# PWR_MGMT.net
KiCad netlist of a schematic drawn in Altium Designer
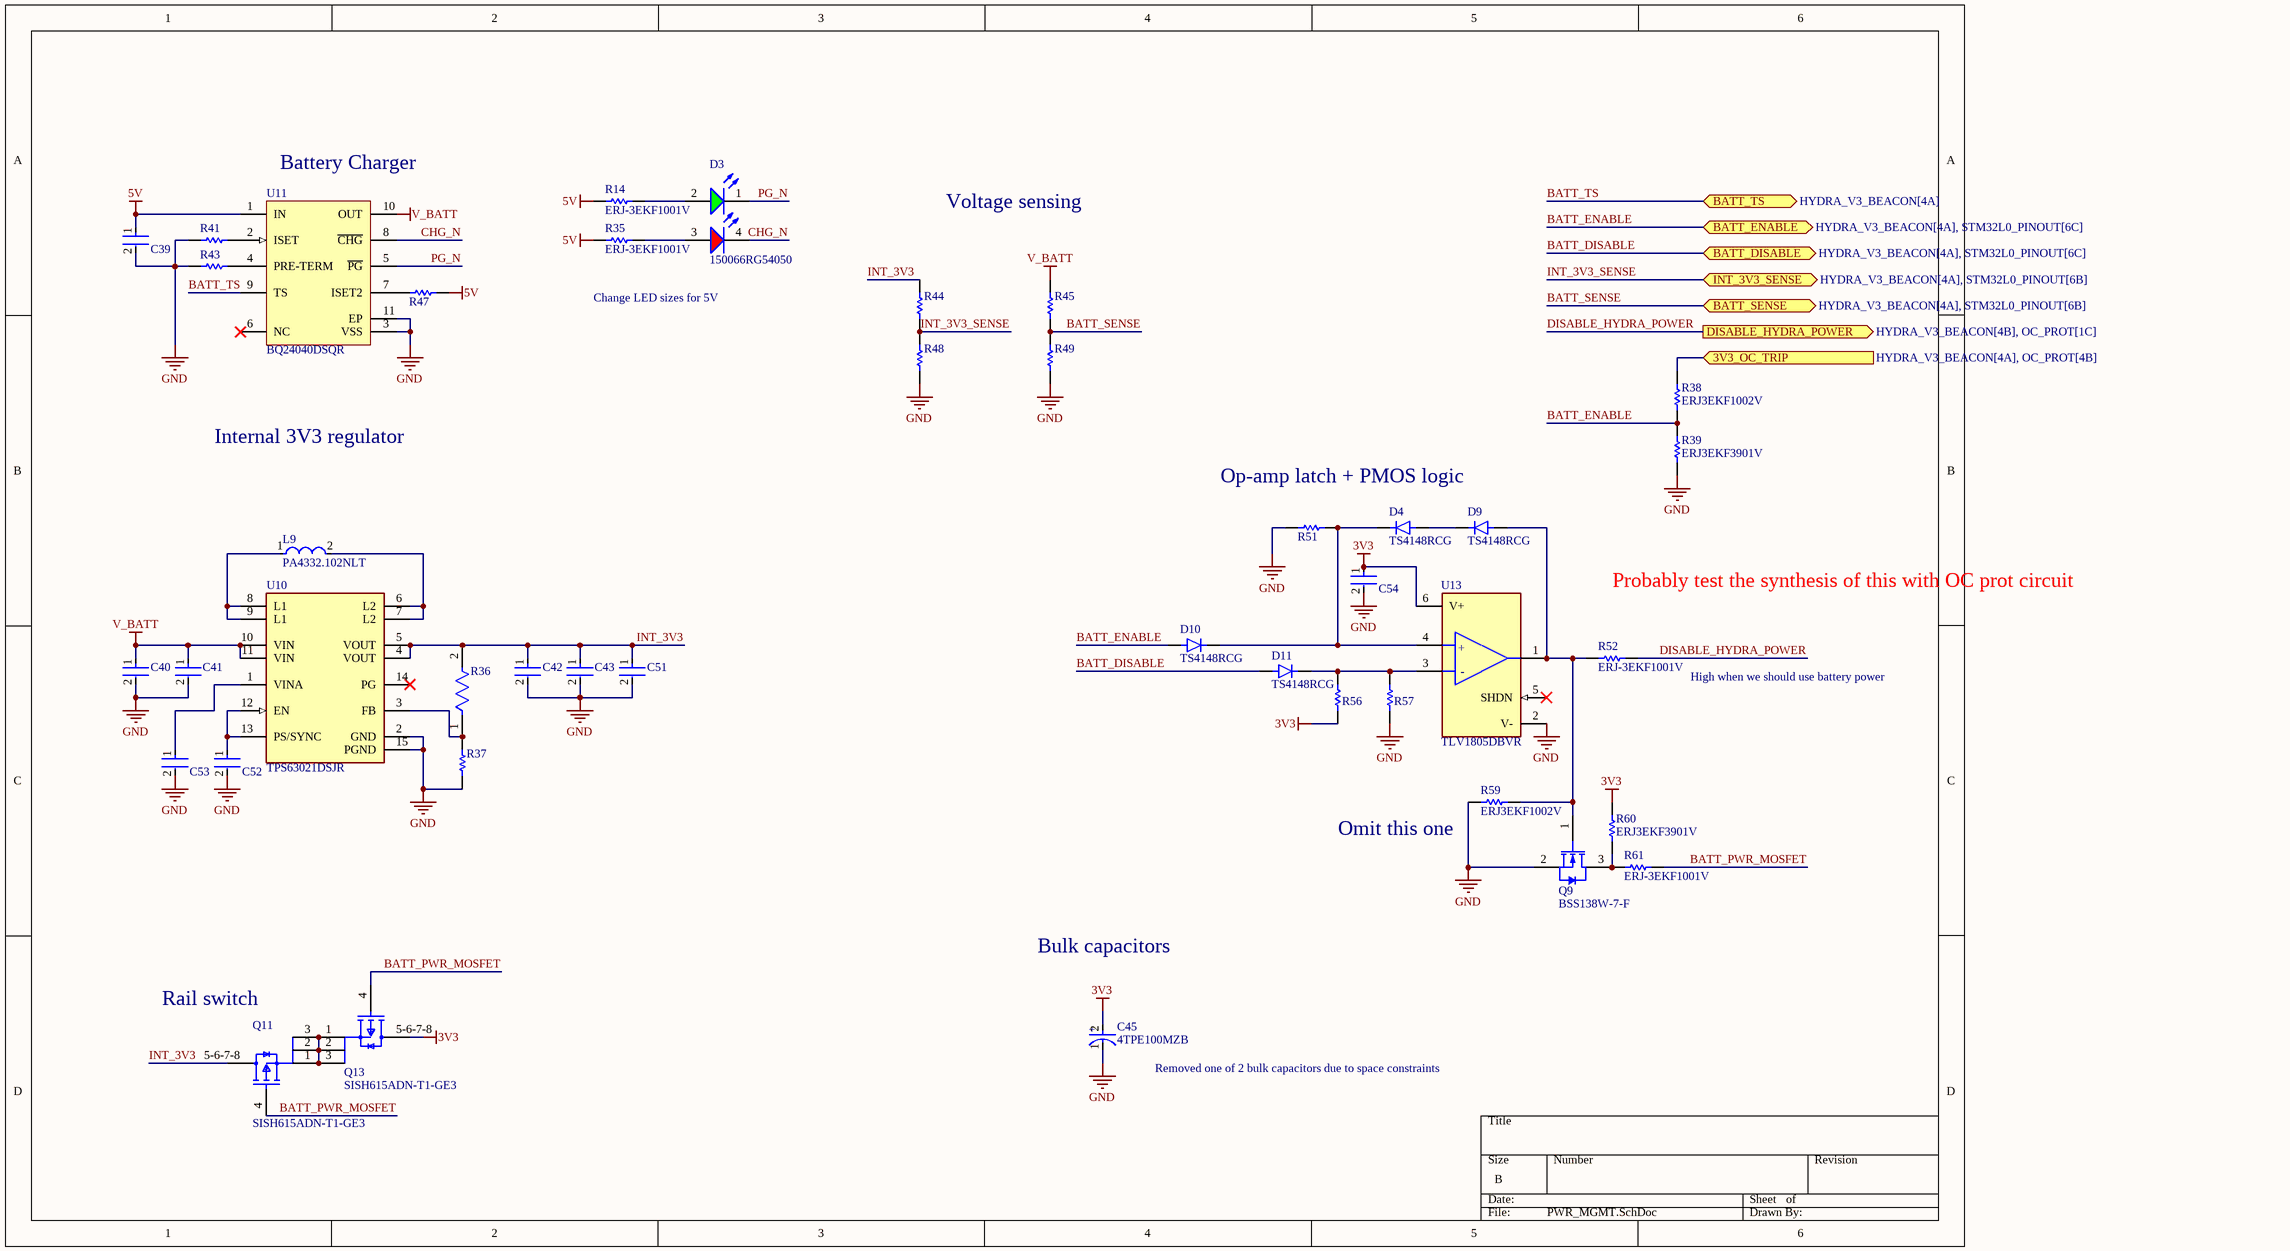
[diagram p0: PWR_MGMT.SchDoc]

(export (version "E")
  (design (tool "Eeschema 10.0.6"))
  (components
    (comp (ref "C39")
      (value "C0402C104K8PACTU")
      (footprint "FP-C0402-BB-MFG")
      (description "CAP CER 0.1UF 10V X5R 0402")
      (fields (field (name "MANUFACTURER") "Kemet") (field (name "TOLERANCE") "0.1"))
      (libsource (lib "Altium Content Vault") (part "b4654b650e69147ec39a6b967a45e02"))
    )
    (comp (ref "C40")
      (value "C0805C106K8PACTU")
      (footprint "FP-C0805C-DG-MFG")
      (description "CAP CER 10UF 10V X5R 0805")
      (fields (field (name "TOLERANCE") "10%") (field (name "MANUFACTURER") "Kemet"))
      (libsource (lib "Altium Content Vault") (part "11868f565c42a9108669ba33697ecf6"))
    )
    (comp (ref "C41")
      (value "C0805C106K8PACTU")
      (footprint "FP-C0805C-DG-MFG")
      (description "CAP CER 10UF 10V X5R 0805")
      (fields (field (name "TOLERANCE") "10%") (field (name "MANUFACTURER") "Kemet"))
      (libsource (lib "Altium Content Vault") (part "11868f565c42a9108669ba33697ecf6"))
    )
    (comp (ref "C42")
      (value "GRM21BR60J226ME39L")
      (footprint "FP-GRM21B-0_15-MFG")
      (description "Chip Multilayer Ceramic Capacitors for General Purpose, 0805, 22uF, X5R, 15%, 20%, 6.3V")
      (fields (field (name "VOLTAGE") "6.3V") (field (name "TOLERANCE") "20%"))
      (libsource (lib "Altium Content Vault") (part "b4654b650e69147ec39a6b967a45e02"))
    )
    (comp (ref "C43")
      (value "GRM21BR60J226ME39L")
      (footprint "FP-GRM21B-0_15-MFG")
      (description "Chip Multilayer Ceramic Capacitors for General Purpose, 0805, 22uF, X5R, 15%, 20%, 6.3V")
      (fields (field (name "VOLTAGE") "6.3V") (field (name "TOLERANCE") "20%"))
      (libsource (lib "Altium Content Vault") (part "b4654b650e69147ec39a6b967a45e02"))
    )
    (comp (ref "C45")
      (value "4TPE100MZB")
      (footprint "FP-POSCAP-B2-MFG")
      (description "Molded Tantalum Polymer Capacitor 100uF 20% 4V life 1000Hours SMD 1411")
      (fields (field (name "VOLTAGE") "4V") (field (name "TOLERANCE") "20%"))
      (libsource (lib "Altium Content Vault") (part "cf48714ba7e38822c1575c7ec0b6d1f"))
    )
    (comp (ref "C51")
      (value "GRM21BR60J226ME39L")
      (footprint "FP-GRM21B-0_15-MFG")
      (description "Chip Multilayer Ceramic Capacitors for General Purpose, 0805, 22uF, X5R, 15%, 20%, 6.3V")
      (fields (field (name "VOLTAGE") "6.3V") (field (name "TOLERANCE") "20%"))
      (libsource (lib "Altium Content Vault") (part "b4654b650e69147ec39a6b967a45e02"))
    )
    (comp (ref "C52")
      (value "C0402C104K8PACTU")
      (footprint "FP-C0402-BB-MFG")
      (description "CAP CER 0.1UF 10V X5R 0402")
      (fields (field (name "MANUFACTURER") "Kemet") (field (name "TOLERANCE") "0.1"))
      (libsource (lib "Altium Content Vault") (part "b4654b650e69147ec39a6b967a45e02"))
    )
    (comp (ref "C53")
      (value "C0402C104K8PACTU")
      (footprint "FP-C0402-BB-MFG")
      (description "CAP CER 0.1UF 10V X5R 0402")
      (fields (field (name "MANUFACTURER") "Kemet") (field (name "TOLERANCE") "0.1"))
      (libsource (lib "Altium Content Vault") (part "b4654b650e69147ec39a6b967a45e02"))
    )
    (comp (ref "C54")
      (value "C0402C104K8PACTU")
      (footprint "FP-C0402-BB-MFG")
      (description "CAP CER 0.1UF 10V X5R 0402")
      (fields (field (name "MANUFACTURER") "Kemet") (field (name "TOLERANCE") "0.1"))
      (libsource (lib "Altium Content Vault") (part "b4654b650e69147ec39a6b967a45e02"))
    )
    (comp (ref "D3")
      (value "150066RG54050")
      (footprint "WL-SBCD_0606")
      (description "Led, Red/Grn, 180Mcd/230Mcd, 624Nm/525Nm Rohs Compliant: Yes")
      (libsource (lib "uORocketry Hardware") (part "WL-SBCD_0606_Red & Green"))
    )
    (comp (ref "D4")
      (value "TS4148RCG")
      (footprint "TS4148RCG-Footprint-1")
      (description "SMD Si-Diode 75V 100mA 0603")
      (libsource (lib "uORocketry Hardware") (part "TS4148RCG"))
    )
    (comp (ref "D9")
      (value "TS4148RCG")
      (footprint "TS4148RCG-Footprint-1")
      (description "SMD Si-Diode 75V 100mA 0603")
      (libsource (lib "uORocketry Hardware") (part "TS4148RCG"))
    )
    (comp (ref "D10")
      (value "TS4148RCG")
      (footprint "TS4148RCG-Footprint-1")
      (description "SMD Si-Diode 75V 100mA 0603")
      (libsource (lib "uORocketry Hardware") (part "TS4148RCG"))
    )
    (comp (ref "D11")
      (value "TS4148RCG")
      (footprint "TS4148RCG-Footprint-1")
      (description "SMD Si-Diode 75V 100mA 0603")
      (libsource (lib "uORocketry Hardware") (part "TS4148RCG"))
    )
    (comp (ref "L9")
      (value "PA4332.102NLT")
      (footprint "FP-PA4332-MFG")
      (description "FIXED IND 1UH 5.8A 26 MOHM SMD")
      (fields (field (name "TOLERANCE") "20%"))
      (libsource (lib "Altium Content Vault") (part "725321dda6339637d4d059423bc1c3c"))
    )
    (comp (ref "Q9")
      (value "BSS138W-7-F")
      (footprint "DIOD-SOT323-3_V")
      (fields (field (name "MANUFACTURER") "DiodesIncorporated"))
      (libsource (lib "Altium Content Vault") (part "NEMOS-GSD-3"))
    )
    (comp (ref "Q11")
      (value "SISH615ADN-T1-GE3")
      (footprint "SISH615ADN-T1-GE3-Footprint-1")
      (description "Trans MOSFET P-CH 20V 22.1A 8-Pin PowerPAK 1212 EP T/R")
      (libsource (lib "uORocketry Hardware") (part "SISH615ADN-T1-GE3-Symbol-1"))
    )
    (comp (ref "Q13")
      (value "SISH615ADN-T1-GE3")
      (footprint "SISH615ADN-T1-GE3-Footprint-1")
      (description "Trans MOSFET P-CH 20V 22.1A 8-Pin PowerPAK 1212 EP T/R")
      (libsource (lib "uORocketry Hardware") (part "SISH615ADN-T1-GE3-Symbol-1"))
    )
    (comp (ref "R14")
      (value "ERJ-3EKF1001V")
      (footprint "RESC1608X55X30LL15T15")
      (fields (field (name "MANUFACTURER") "Panasonic"))
      (libsource (lib "Altium Content Vault") (part "RES"))
    )
    (comp (ref "R35")
      (value "ERJ-3EKF1001V")
      (footprint "RESC1608X55X30LL15T15")
      (fields (field (name "MANUFACTURER") "Panasonic"))
      (libsource (lib "Altium Content Vault") (part "RES"))
    )
    (comp (ref "R36")
      (value "ERJ-3EKF1004V")
      (footprint "FP-ERJ3EK-IPC_C")
      (description "RES SMD 1M OHM 1% 1/10W 0603")
      (fields (field (name "TOLERANCE") "1%"))
      (libsource (lib "Altium Content Vault") (part "1029c3af85768c4190bb7ad29bc67b5"))
    )
    (comp (ref "R37")
      (value "ERJ3EKF1803V")
      (footprint "RESC1608X55X30LL15T15")
      (fields (field (name "MANUFACTURER") "Panasonic"))
      (libsource (lib "Altium Content Vault") (part "RES"))
    )
    (comp (ref "R38")
      (value "ERJ3EKF1002V")
      (footprint "RESC1609X55X30LL15T15")
      (description "Chip Resistor, 10 KOhm, +/- 1%, 0.1 W, -55 to 155 degC, 0603 (1608 Metric), RoHS, Tape and Reel")
      (fields (field (name "TOLERANCE") "1%") (field (name "MANUFACTURER") "Panasonic"))
      (libsource (lib "Altium Content Vault") (part "RES-2"))
    )
    (comp (ref "R39")
      (value "ERJ3EKF3901V")
      (footprint "RESC1608X55X30ML15T15")
      (fields (field (name "MANUFACTURER") "Panasonic"))
      (libsource (lib "Altium Content Vault") (part "RES"))
    )
    (comp (ref "R41")
      (value "ERJ-3EKF1001V")
      (footprint "RESC1608X55X30LL15T15")
      (fields (field (name "MANUFACTURER") "Panasonic"))
      (libsource (lib "Altium Content Vault") (part "RES"))
    )
    (comp (ref "R43")
      (value "ERJ-3EKF1001V")
      (footprint "RESC1608X55X30LL15T15")
      (fields (field (name "MANUFACTURER") "Panasonic"))
      (libsource (lib "Altium Content Vault") (part "RES"))
    )
    (comp (ref "R44")
      (value "ERJ3EKF1002V")
      (footprint "RESC1609X55X30LL15T15")
      (description "Chip Resistor, 10 KOhm, +/- 1%, 0.1 W, -55 to 155 degC, 0603 (1608 Metric), RoHS, Tape and Reel")
      (fields (field (name "TOLERANCE") "1%") (field (name "MANUFACTURER") "Panasonic"))
      (libsource (lib "Altium Content Vault") (part "RES-2"))
    )
    (comp (ref "R45")
      (value "ERJ3EKF1002V")
      (footprint "RESC1609X55X30LL15T15")
      (description "Chip Resistor, 10 KOhm, +/- 1%, 0.1 W, -55 to 155 degC, 0603 (1608 Metric), RoHS, Tape and Reel")
      (fields (field (name "TOLERANCE") "1%") (field (name "MANUFACTURER") "Panasonic"))
      (libsource (lib "Altium Content Vault") (part "RES-2"))
    )
    (comp (ref "R47")
      (value "ERJ3EKF1002V")
      (footprint "RESC1609X55X30LL15T15")
      (description "Chip Resistor, 10 KOhm, +/- 1%, 0.1 W, -55 to 155 degC, 0603 (1608 Metric), RoHS, Tape and Reel")
      (fields (field (name "TOLERANCE") "1%") (field (name "MANUFACTURER") "Panasonic"))
      (libsource (lib "Altium Content Vault") (part "RES-2"))
    )
    (comp (ref "R48")
      (value "ERJ3EKF1002V")
      (footprint "RESC1609X55X30LL15T15")
      (description "Chip Resistor, 10 KOhm, +/- 1%, 0.1 W, -55 to 155 degC, 0603 (1608 Metric), RoHS, Tape and Reel")
      (fields (field (name "TOLERANCE") "1%") (field (name "MANUFACTURER") "Panasonic"))
      (libsource (lib "Altium Content Vault") (part "RES-2"))
    )
    (comp (ref "R49")
      (value "ERJ3EKF1002V")
      (footprint "RESC1609X55X30LL15T15")
      (description "Chip Resistor, 10 KOhm, +/- 1%, 0.1 W, -55 to 155 degC, 0603 (1608 Metric), RoHS, Tape and Reel")
      (fields (field (name "TOLERANCE") "1%") (field (name "MANUFACTURER") "Panasonic"))
      (libsource (lib "Altium Content Vault") (part "RES-2"))
    )
    (comp (ref "R51")
      (value "ERJ3EKF1002V")
      (footprint "RESC1609X55X30LL15T15")
      (description "Chip Resistor, 10 KOhm, +/- 1%, 0.1 W, -55 to 155 degC, 0603 (1608 Metric), RoHS, Tape and Reel")
      (fields (field (name "TOLERANCE") "1%") (field (name "MANUFACTURER") "Panasonic"))
      (libsource (lib "Altium Content Vault") (part "RES-2"))
    )
    (comp (ref "R52")
      (value "ERJ-3EKF1001V")
      (footprint "RESC1608X55X30LL15T15")
      (fields (field (name "MANUFACTURER") "Panasonic"))
      (libsource (lib "Altium Content Vault") (part "RES"))
    )
    (comp (ref "R56")
      (value "ERJ3EKF1002V")
      (footprint "RESC1609X55X30LL15T15")
      (description "Chip Resistor, 10 KOhm, +/- 1%, 0.1 W, -55 to 155 degC, 0603 (1608 Metric), RoHS, Tape and Reel")
      (fields (field (name "TOLERANCE") "1%") (field (name "MANUFACTURER") "Panasonic"))
      (libsource (lib "Altium Content Vault") (part "RES-2"))
    )
    (comp (ref "R57")
      (value "ERJ3EKF1002V")
      (footprint "RESC1609X55X30LL15T15")
      (description "Chip Resistor, 10 KOhm, +/- 1%, 0.1 W, -55 to 155 degC, 0603 (1608 Metric), RoHS, Tape and Reel")
      (fields (field (name "TOLERANCE") "1%") (field (name "MANUFACTURER") "Panasonic"))
      (libsource (lib "Altium Content Vault") (part "RES-2"))
    )
    (comp (ref "R59")
      (value "ERJ3EKF1002V")
      (footprint "RESC1609X55X30LL15T15")
      (description "Chip Resistor, 10 KOhm, +/- 1%, 0.1 W, -55 to 155 degC, 0603 (1608 Metric), RoHS, Tape and Reel")
      (fields (field (name "TOLERANCE") "1%") (field (name "MANUFACTURER") "Panasonic"))
      (libsource (lib "Altium Content Vault") (part "RES-2"))
    )
    (comp (ref "R60")
      (value "ERJ3EKF3901V")
      (footprint "RESC1608X55X30ML15T15")
      (fields (field (name "MANUFACTURER") "Panasonic"))
      (libsource (lib "Altium Content Vault") (part "RES"))
    )
    (comp (ref "R61")
      (value "ERJ-3EKF1001V")
      (footprint "RESC1608X55X30LL15T15")
      (fields (field (name "MANUFACTURER") "Panasonic"))
      (libsource (lib "Altium Content Vault") (part "RES"))
    )
    (comp (ref "U10")
      (value "TPS63021DSJR")
      (footprint "FP-DSJ0014A-MFG")
      (description "IC REG BCK BST 3.3V 3.5A 14VSON")
      (fields
        (field (name "MANUFACTURER") "Texas Instruments")
        (field (name "OCTOPART") "https://octopart.com/tps63021dsjr-texas+instruments-17659431")
      )
      (libsource (lib "Altium Content Vault") (part "65dfafb52e5c3d3d60c9dfe8dd4b050"))
    )
    (comp (ref "U11")
      (value "BQ24040DSQR")
      (footprint "DSQ0010A_V")
      (fields (field (name "MANUFACTURER") "Texas Instruments"))
      (libsource (lib "Altium Content Vault") (part "TI-BQ24040DSQ10-1500X900TP"))
    )
    (comp (ref "U13")
      (value "TLV1805DBVR")
      (footprint "FP-DBV0006A-IPC_C")
      (description "40V, RAIL-TO-RAIL INPUT, PUSH-PU")
      (libsource (lib "Altium Content Vault") (part "c7aa3bc3dbf0dc8b0b0354779bd1228"))
    )
  )
  (nets
    (net (code "1") (name "/3V3_OC_TRIP") (class "Default")
      (node (ref "R38") (pin "2") (pinfunction "2_2") (pintype "passive"))
    )
    (net (code "2") (name "/BATT_DISABLE") (class "Default")
      (node (ref "D11") (pin "A") (pinfunction "A_A") (pintype "passive"))
    )
    (net (code "3") (name "/BATT_ENABLE") (class "Default")
      (node (ref "D10") (pin "A") (pinfunction "A_A") (pintype "passive"))
      (node (ref "R38") (pin "1") (pinfunction "1_1") (pintype "passive"))
      (node (ref "R39") (pin "2") (pinfunction "2_2") (pintype "passive"))
    )
    (net (code "4") (name "/BATT_PWR_MOSFET") (class "Default")
      (node (ref "Q11") (pin "4") (pinfunction "G_4") (pintype "passive"))
      (node (ref "Q13") (pin "4") (pinfunction "G_4") (pintype "passive"))
      (node (ref "R61") (pin "2") (pinfunction "2_2") (pintype "passive"))
    )
    (net (code "5") (name "/BATT_SENSE") (class "Default")
      (node (ref "R45") (pin "1") (pinfunction "1_1") (pintype "passive"))
      (node (ref "R49") (pin "2") (pinfunction "2_2") (pintype "passive"))
    )
    (net (code "6") (name "/BATT_TS") (class "Default")
      (node (ref "U11") (pin "9") (pinfunction "TS_9") (pintype "passive"))
    )
    (net (code "7") (name "/CHG_N") (class "Default")
      (node (ref "D3") (pin "4") (pinfunction "K_4") (pintype "passive"))
      (node (ref "U11") (pin "8") (pinfunction "~{CHG}_8") (pintype "tri_state"))
    )
    (net (code "8") (name "/DISABLE_HYDRA_POWER") (class "Default")
      (node (ref "R52") (pin "1") (pinfunction "1_1") (pintype "passive"))
    )
    (net (code "9") (name "/INT_3V3") (class "Default")
      (node (ref "C42") (pin "1") (pinfunction "1_1") (pintype "passive"))
      (node (ref "C43") (pin "1") (pinfunction "1_1") (pintype "passive"))
      (node (ref "C51") (pin "1") (pinfunction "1_1") (pintype "passive"))
      (node (ref "Q11") (pin "5-6-7-8") (pinfunction "D_5-6-7-8") (pintype "passive"))
      (node (ref "R36") (pin "2") (pinfunction "2_2") (pintype "passive"))
      (node (ref "R44") (pin "2") (pinfunction "2_2") (pintype "passive"))
      (node (ref "U10") (pin "4") (pinfunction "VOUT_4") (pintype "power_in"))
      (node (ref "U10") (pin "5") (pinfunction "VOUT_5") (pintype "power_in"))
    )
    (net (code "10") (name "/INT_3V3_SENSE") (class "Default")
      (node (ref "R44") (pin "1") (pinfunction "1_1") (pintype "passive"))
      (node (ref "R48") (pin "2") (pinfunction "2_2") (pintype "passive"))
    )
    (net (code "11") (name "/PG_N") (class "Default")
      (node (ref "D3") (pin "1") (pinfunction "K_1") (pintype "passive"))
      (node (ref "U11") (pin "5") (pinfunction "~{PG}_5") (pintype "tri_state"))
    )
    (net (code "12") (name "3V3") (class "Default")
      (node (ref "C45") (pin "2") (pinfunction "A_2") (pintype "passive"))
      (node (ref "C54") (pin "1") (pinfunction "1_1") (pintype "passive"))
      (node (ref "Q13") (pin "5-6-7-8") (pinfunction "D_5-6-7-8") (pintype "passive"))
      (node (ref "R56") (pin "1") (pinfunction "1_1") (pintype "passive"))
      (node (ref "R60") (pin "2") (pinfunction "2_2") (pintype "passive"))
      (node (ref "U13") (pin "6") (pinfunction "V+_6") (pintype "power_in"))
    )
    (net (code "13") (name "5V") (class "Default")
      (node (ref "C39") (pin "1") (pinfunction "1_1") (pintype "passive"))
      (node (ref "R14") (pin "1") (pinfunction "1_1") (pintype "passive"))
      (node (ref "R35") (pin "1") (pinfunction "1_1") (pintype "passive"))
      (node (ref "R47") (pin "2") (pinfunction "2_2") (pintype "passive"))
      (node (ref "U11") (pin "1") (pinfunction "IN_1") (pintype "power_in"))
    )
    (net (code "14") (name "GND") (class "Default")
      (node (ref "C39") (pin "2") (pinfunction "2_2") (pintype "passive"))
      (node (ref "C40") (pin "2") (pinfunction "2_2") (pintype "passive"))
      (node (ref "C41") (pin "2") (pinfunction "2_2") (pintype "passive"))
      (node (ref "C42") (pin "2") (pinfunction "2_2") (pintype "passive"))
      (node (ref "C43") (pin "2") (pinfunction "2_2") (pintype "passive"))
      (node (ref "C45") (pin "1") (pinfunction "C_1") (pintype "passive"))
      (node (ref "C51") (pin "2") (pinfunction "2_2") (pintype "passive"))
      (node (ref "C52") (pin "2") (pinfunction "2_2") (pintype "passive"))
      (node (ref "C53") (pin "2") (pinfunction "2_2") (pintype "passive"))
      (node (ref "C54") (pin "2") (pinfunction "2_2") (pintype "passive"))
      (node (ref "Q9") (pin "2") (pinfunction "S_2") (pintype "passive"))
      (node (ref "R37") (pin "1") (pinfunction "1_1") (pintype "passive"))
      (node (ref "R39") (pin "1") (pinfunction "1_1") (pintype "passive"))
      (node (ref "R41") (pin "2") (pinfunction "2_2") (pintype "passive"))
      (node (ref "R43") (pin "2") (pinfunction "2_2") (pintype "passive"))
      (node (ref "R48") (pin "1") (pinfunction "1_1") (pintype "passive"))
      (node (ref "R49") (pin "1") (pinfunction "1_1") (pintype "passive"))
      (node (ref "R51") (pin "2") (pinfunction "2_2") (pintype "passive"))
      (node (ref "R57") (pin "1") (pinfunction "1_1") (pintype "passive"))
      (node (ref "R59") (pin "2") (pinfunction "2_2") (pintype "passive"))
      (node (ref "U10") (pin "15") (pinfunction "PGND_15") (pintype "power_in"))
      (node (ref "U10") (pin "2") (pinfunction "GND_2") (pintype "power_in"))
      (node (ref "U11") (pin "11") (pinfunction "EP_11") (pintype "power_in"))
      (node (ref "U11") (pin "3") (pinfunction "VSS_3") (pintype "power_in"))
      (node (ref "U13") (pin "2") (pinfunction "V-_2") (pintype "power_in"))
    )
    (net (code "15") (name "Net-(D3-A-Pad2)") (class "Default")
      (node (ref "D3") (pin "2") (pinfunction "A_2") (pintype "passive"))
      (node (ref "R14") (pin "2") (pinfunction "2_2") (pintype "passive"))
    )
    (net (code "16") (name "Net-(D3-A-Pad3)") (class "Default")
      (node (ref "D3") (pin "3") (pinfunction "A_3") (pintype "passive"))
      (node (ref "R35") (pin "2") (pinfunction "2_2") (pintype "passive"))
    )
    (net (code "17") (name "Net-(D9-K)") (class "Default")
      (node (ref "D4") (pin "A") (pinfunction "A_A") (pintype "passive"))
      (node (ref "D9") (pin "C") (pinfunction "K_C") (pintype "passive"))
    )
    (net (code "18") (name "Net-(D10-K)") (class "Default")
      (node (ref "D10") (pin "C") (pinfunction "K_C") (pintype "passive"))
      (node (ref "D4") (pin "C") (pinfunction "K_C") (pintype "passive"))
      (node (ref "R51") (pin "1") (pinfunction "1_1") (pintype "passive"))
      (node (ref "U13") (pin "4") (pinfunction "+IN_4") (pintype "tri_state"))
    )
    (net (code "19") (name "Net-(D11-K)") (class "Default")
      (node (ref "D11") (pin "C") (pinfunction "K_C") (pintype "passive"))
      (node (ref "R56") (pin "2") (pinfunction "2_2") (pintype "passive"))
      (node (ref "R57") (pin "2") (pinfunction "2_2") (pintype "passive"))
      (node (ref "U13") (pin "3") (pinfunction "-IN_3") (pintype "tri_state"))
    )
    (net (code "20") (name "Net-(L9-Pad1)") (class "Default")
      (node (ref "L9") (pin "1") (pinfunction "1_1") (pintype "passive"))
      (node (ref "U10") (pin "8") (pinfunction "L1_8") (pintype "passive"))
      (node (ref "U10") (pin "9") (pinfunction "L1_9") (pintype "passive"))
    )
    (net (code "21") (name "Net-(L9-Pad2)") (class "Default")
      (node (ref "L9") (pin "2") (pinfunction "2_2") (pintype "passive"))
      (node (ref "U10") (pin "6") (pinfunction "L2_6") (pintype "passive"))
      (node (ref "U10") (pin "7") (pinfunction "L2_7") (pintype "passive"))
    )
    (net (code "22") (name "Net-(Q9-D)") (class "Default")
      (node (ref "Q9") (pin "3") (pinfunction "D_3") (pintype "passive"))
      (node (ref "R60") (pin "1") (pinfunction "1_1") (pintype "passive"))
      (node (ref "R61") (pin "1") (pinfunction "1_1") (pintype "passive"))
    )
    (net (code "23") (name "Net-(Q9-G)") (class "Default")
      (node (ref "D9") (pin "A") (pinfunction "A_A") (pintype "passive"))
      (node (ref "Q9") (pin "1") (pinfunction "G_1") (pintype "passive"))
      (node (ref "R52") (pin "2") (pinfunction "2_2") (pintype "passive"))
      (node (ref "R59") (pin "1") (pinfunction "1_1") (pintype "passive"))
      (node (ref "U13") (pin "1") (pinfunction "OUT_1") (pintype "passive"))
    )
    (net (code "24") (name "Net-(Q11-S-Pad1)") (class "Default")
      (node (ref "Q11") (pin "1") (pinfunction "S_1") (pintype "passive"))
      (node (ref "Q11") (pin "2") (pinfunction "S_2") (pintype "passive"))
      (node (ref "Q11") (pin "3") (pinfunction "S_3") (pintype "passive"))
      (node (ref "Q13") (pin "1") (pinfunction "S_1") (pintype "passive"))
      (node (ref "Q13") (pin "2") (pinfunction "S_2") (pintype "passive"))
      (node (ref "Q13") (pin "3") (pinfunction "S_3") (pintype "passive"))
    )
    (net (code "25") (name "Net-(U10-EN)") (class "Default")
      (node (ref "C52") (pin "1") (pinfunction "1_1") (pintype "passive"))
      (node (ref "U10") (pin "12") (pinfunction "EN_12") (pintype "input"))
      (node (ref "U10") (pin "13") (pinfunction "PS/SYNC_13") (pintype "passive"))
    )
    (net (code "26") (name "Net-(U10-FB)") (class "Default")
      (node (ref "R36") (pin "1") (pinfunction "1_1") (pintype "passive"))
      (node (ref "R37") (pin "2") (pinfunction "2_2") (pintype "passive"))
      (node (ref "U10") (pin "3") (pinfunction "FB_3") (pintype "passive"))
    )
    (net (code "27") (name "Net-(U10-VINA)") (class "Default")
      (node (ref "C53") (pin "1") (pinfunction "1_1") (pintype "passive"))
      (node (ref "U10") (pin "1") (pinfunction "VINA_1") (pintype "power_in"))
    )
    (net (code "28") (name "Net-(U11-ISET)") (class "Default")
      (node (ref "R41") (pin "1") (pinfunction "1_1") (pintype "passive"))
      (node (ref "U11") (pin "2") (pinfunction "ISET_2") (pintype "input"))
    )
    (net (code "29") (name "Net-(U11-ISET2)") (class "Default")
      (node (ref "R47") (pin "1") (pinfunction "1_1") (pintype "passive"))
      (node (ref "U11") (pin "7") (pinfunction "ISET2_7") (pintype "passive"))
    )
    (net (code "30") (name "Net-(U11-PRE-TERM)") (class "Default")
      (node (ref "R43") (pin "1") (pinfunction "1_1") (pintype "passive"))
      (node (ref "U11") (pin "4") (pinfunction "PRE-TERM_4") (pintype "passive"))
    )
    (net (code "31") (name "V_BATT") (class "Default")
      (node (ref "C40") (pin "1") (pinfunction "1_1") (pintype "passive"))
      (node (ref "C41") (pin "1") (pinfunction "1_1") (pintype "passive"))
      (node (ref "R45") (pin "2") (pinfunction "2_2") (pintype "passive"))
      (node (ref "U10") (pin "10") (pinfunction "VIN_10") (pintype "power_in"))
      (node (ref "U10") (pin "11") (pinfunction "VIN_11") (pintype "power_in"))
      (node (ref "U11") (pin "10") (pinfunction "OUT_10") (pintype "power_in"))
    )
    (net (code "32") (name "unconnected-(U10-PG-Pad14)") (class "Default")
      (node (ref "U10") (pin "14") (pinfunction "PG_14") (pintype "open_collector+no_connect"))
    )
    (net (code "33") (name "unconnected-(U11-NC-Pad6)") (class "Default")
      (node (ref "U11") (pin "6") (pinfunction "NC_6") (pintype "passive+no_connect"))
    )
    (net (code "34") (name "unconnected-(U13-SHDN-Pad5)") (class "Default")
      (node (ref "U13") (pin "5") (pinfunction "SHDN_5") (pintype "input+no_connect"))
    )
  )
)
